# module_SX1272.net
KiCad netlist of a schematic drawn in EAGLE
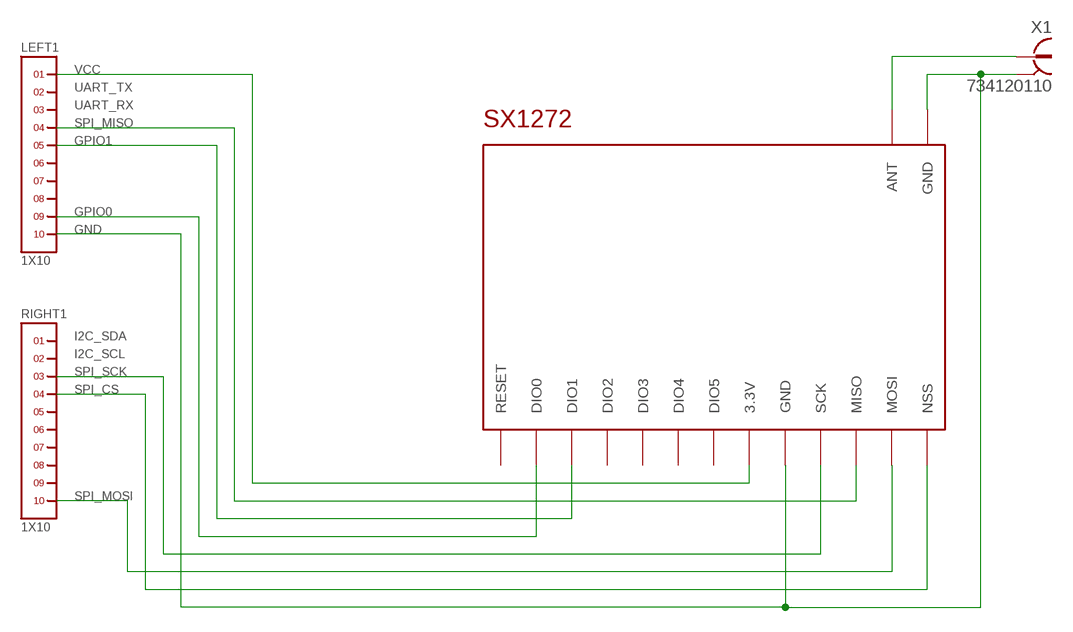
[diagram p0: schematic, sheet 1]

(export (version "E")
  (design (tool "Eeschema 10.0.6"))
  (components
    (comp (ref "LEFT1")
      (value "1X10")
      (footprint "eagle-import:1X10")
      (libsource (lib "eagle-import") (part "1X10"))
    )
    (comp (ref "RIGHT1")
      (value "1X10")
      (footprint "eagle-import:1X10")
      (libsource (lib "eagle-import") (part "1X10"))
    )
    (comp (ref "U$1")
      (value "SX1272")
      (footprint "eagle-import:SX1272")
      (libsource (lib "eagle-import") (part "SX1272"))
    )
    (comp (ref "X1")
      (value "734120110")
      (footprint "eagle-import:734120110")
      (libsource (lib "eagle-import") (part "734120110"))
    )
  )
  (nets
    (net (code "1") (name "Net-(LEFT1-Pad1)") (class "Default")
      (node (ref "LEFT1") (pin "1") (pinfunction "1_1") (pintype "bidirectional"))
      (node (ref "U$1") (pin "3.3V") (pinfunction "3.3V_3.3V") (pintype "bidirectional"))
    )
    (net (code "2") (name "Net-(LEFT1-Pad4)") (class "Default")
      (node (ref "LEFT1") (pin "4") (pinfunction "4_4") (pintype "bidirectional"))
      (node (ref "U$1") (pin "MISO") (pinfunction "MISO_MISO") (pintype "bidirectional"))
    )
    (net (code "3") (name "Net-(LEFT1-Pad5)") (class "Default")
      (node (ref "LEFT1") (pin "5") (pinfunction "5_5") (pintype "bidirectional"))
      (node (ref "U$1") (pin "DIO1") (pinfunction "DIO1_DIO1") (pintype "bidirectional"))
    )
    (net (code "4") (name "Net-(LEFT1-Pad9)") (class "Default")
      (node (ref "LEFT1") (pin "9") (pinfunction "9_9") (pintype "bidirectional"))
      (node (ref "U$1") (pin "DIO0") (pinfunction "DIO0_DIO0") (pintype "bidirectional"))
    )
    (net (code "5") (name "Net-(LEFT1-Pad10)") (class "Default")
      (node (ref "LEFT1") (pin "10") (pinfunction "10_10") (pintype "bidirectional"))
      (node (ref "U$1") (pin "GND@1") (pinfunction "GND_GND@1") (pintype "bidirectional"))
      (node (ref "U$1") (pin "GND@2") (pinfunction "GND_GND@2") (pintype "bidirectional"))
      (node (ref "X1") (pin "S@1") (pinfunction "2_S@1") (pintype "passive"))
      (node (ref "X1") (pin "S@2") (pinfunction "2_S@2") (pintype "passive"))
      (node (ref "X1") (pin "S@3") (pinfunction "2_S@3") (pintype "passive"))
    )
    (net (code "6") (name "Net-(RIGHT1-Pad3)") (class "Default")
      (node (ref "RIGHT1") (pin "3") (pinfunction "3_3") (pintype "bidirectional"))
      (node (ref "U$1") (pin "SCK") (pinfunction "SCK_SCK") (pintype "bidirectional"))
    )
    (net (code "7") (name "Net-(RIGHT1-Pad4)") (class "Default")
      (node (ref "RIGHT1") (pin "4") (pinfunction "4_4") (pintype "bidirectional"))
      (node (ref "U$1") (pin "NSS") (pinfunction "NSS_NSS") (pintype "bidirectional"))
    )
    (net (code "8") (name "Net-(RIGHT1-Pad10)") (class "Default")
      (node (ref "RIGHT1") (pin "10") (pinfunction "10_10") (pintype "bidirectional"))
      (node (ref "U$1") (pin "MOSI") (pinfunction "MOSI_MOSI") (pintype "bidirectional"))
    )
    (net (code "9") (name "Net-(U$1-PadANT)") (class "Default")
      (node (ref "U$1") (pin "ANT") (pinfunction "ANT_ANT") (pintype "bidirectional"))
      (node (ref "X1") (pin "1") (pinfunction "1_1") (pintype "passive"))
    )
    (net (code "10") (name "unconnected-(LEFT1-Pad2)") (class "Default")
      (node (ref "LEFT1") (pin "2") (pinfunction "2_2") (pintype "bidirectional"))
    )
    (net (code "11") (name "unconnected-(LEFT1-Pad3)") (class "Default")
      (node (ref "LEFT1") (pin "3") (pinfunction "3_3") (pintype "bidirectional"))
    )
    (net (code "12") (name "unconnected-(LEFT1-Pad6)") (class "Default")
      (node (ref "LEFT1") (pin "6") (pinfunction "6_6") (pintype "bidirectional"))
    )
    (net (code "13") (name "unconnected-(LEFT1-Pad7)") (class "Default")
      (node (ref "LEFT1") (pin "7") (pinfunction "7_7") (pintype "bidirectional"))
    )
    (net (code "14") (name "unconnected-(LEFT1-Pad8)") (class "Default")
      (node (ref "LEFT1") (pin "8") (pinfunction "8_8") (pintype "bidirectional"))
    )
    (net (code "15") (name "unconnected-(RIGHT1-Pad1)") (class "Default")
      (node (ref "RIGHT1") (pin "1") (pinfunction "1_1") (pintype "bidirectional"))
    )
    (net (code "16") (name "unconnected-(RIGHT1-Pad2)") (class "Default")
      (node (ref "RIGHT1") (pin "2") (pinfunction "2_2") (pintype "bidirectional"))
    )
    (net (code "17") (name "unconnected-(RIGHT1-Pad5)") (class "Default")
      (node (ref "RIGHT1") (pin "5") (pinfunction "5_5") (pintype "bidirectional"))
    )
    (net (code "18") (name "unconnected-(RIGHT1-Pad6)") (class "Default")
      (node (ref "RIGHT1") (pin "6") (pinfunction "6_6") (pintype "bidirectional"))
    )
    (net (code "19") (name "unconnected-(RIGHT1-Pad7)") (class "Default")
      (node (ref "RIGHT1") (pin "7") (pinfunction "7_7") (pintype "bidirectional"))
    )
    (net (code "20") (name "unconnected-(RIGHT1-Pad8)") (class "Default")
      (node (ref "RIGHT1") (pin "8") (pinfunction "8_8") (pintype "bidirectional"))
    )
    (net (code "21") (name "unconnected-(RIGHT1-Pad9)") (class "Default")
      (node (ref "RIGHT1") (pin "9") (pinfunction "9_9") (pintype "bidirectional"))
    )
    (net (code "22") (name "unconnected-(U$1-PadDIO2)") (class "Default")
      (node (ref "U$1") (pin "DIO2") (pinfunction "DIO2_DIO2") (pintype "bidirectional"))
    )
    (net (code "23") (name "unconnected-(U$1-PadDIO3)") (class "Default")
      (node (ref "U$1") (pin "DIO3") (pinfunction "DIO3_DIO3") (pintype "bidirectional"))
    )
    (net (code "24") (name "unconnected-(U$1-PadDIO4)") (class "Default")
      (node (ref "U$1") (pin "DIO4") (pinfunction "DIO4_DIO4") (pintype "bidirectional"))
    )
    (net (code "25") (name "unconnected-(U$1-PadDIO5)") (class "Default")
      (node (ref "U$1") (pin "DIO5") (pinfunction "DIO5_DIO5") (pintype "bidirectional"))
    )
    (net (code "26") (name "unconnected-(U$1-PadRESET)") (class "Default")
      (node (ref "U$1") (pin "RESET") (pinfunction "RESET_RESET") (pintype "bidirectional"))
    )
  )
)
